# vent_bjt2.net
KiCad netlist of a schematic drawn in EAGLE
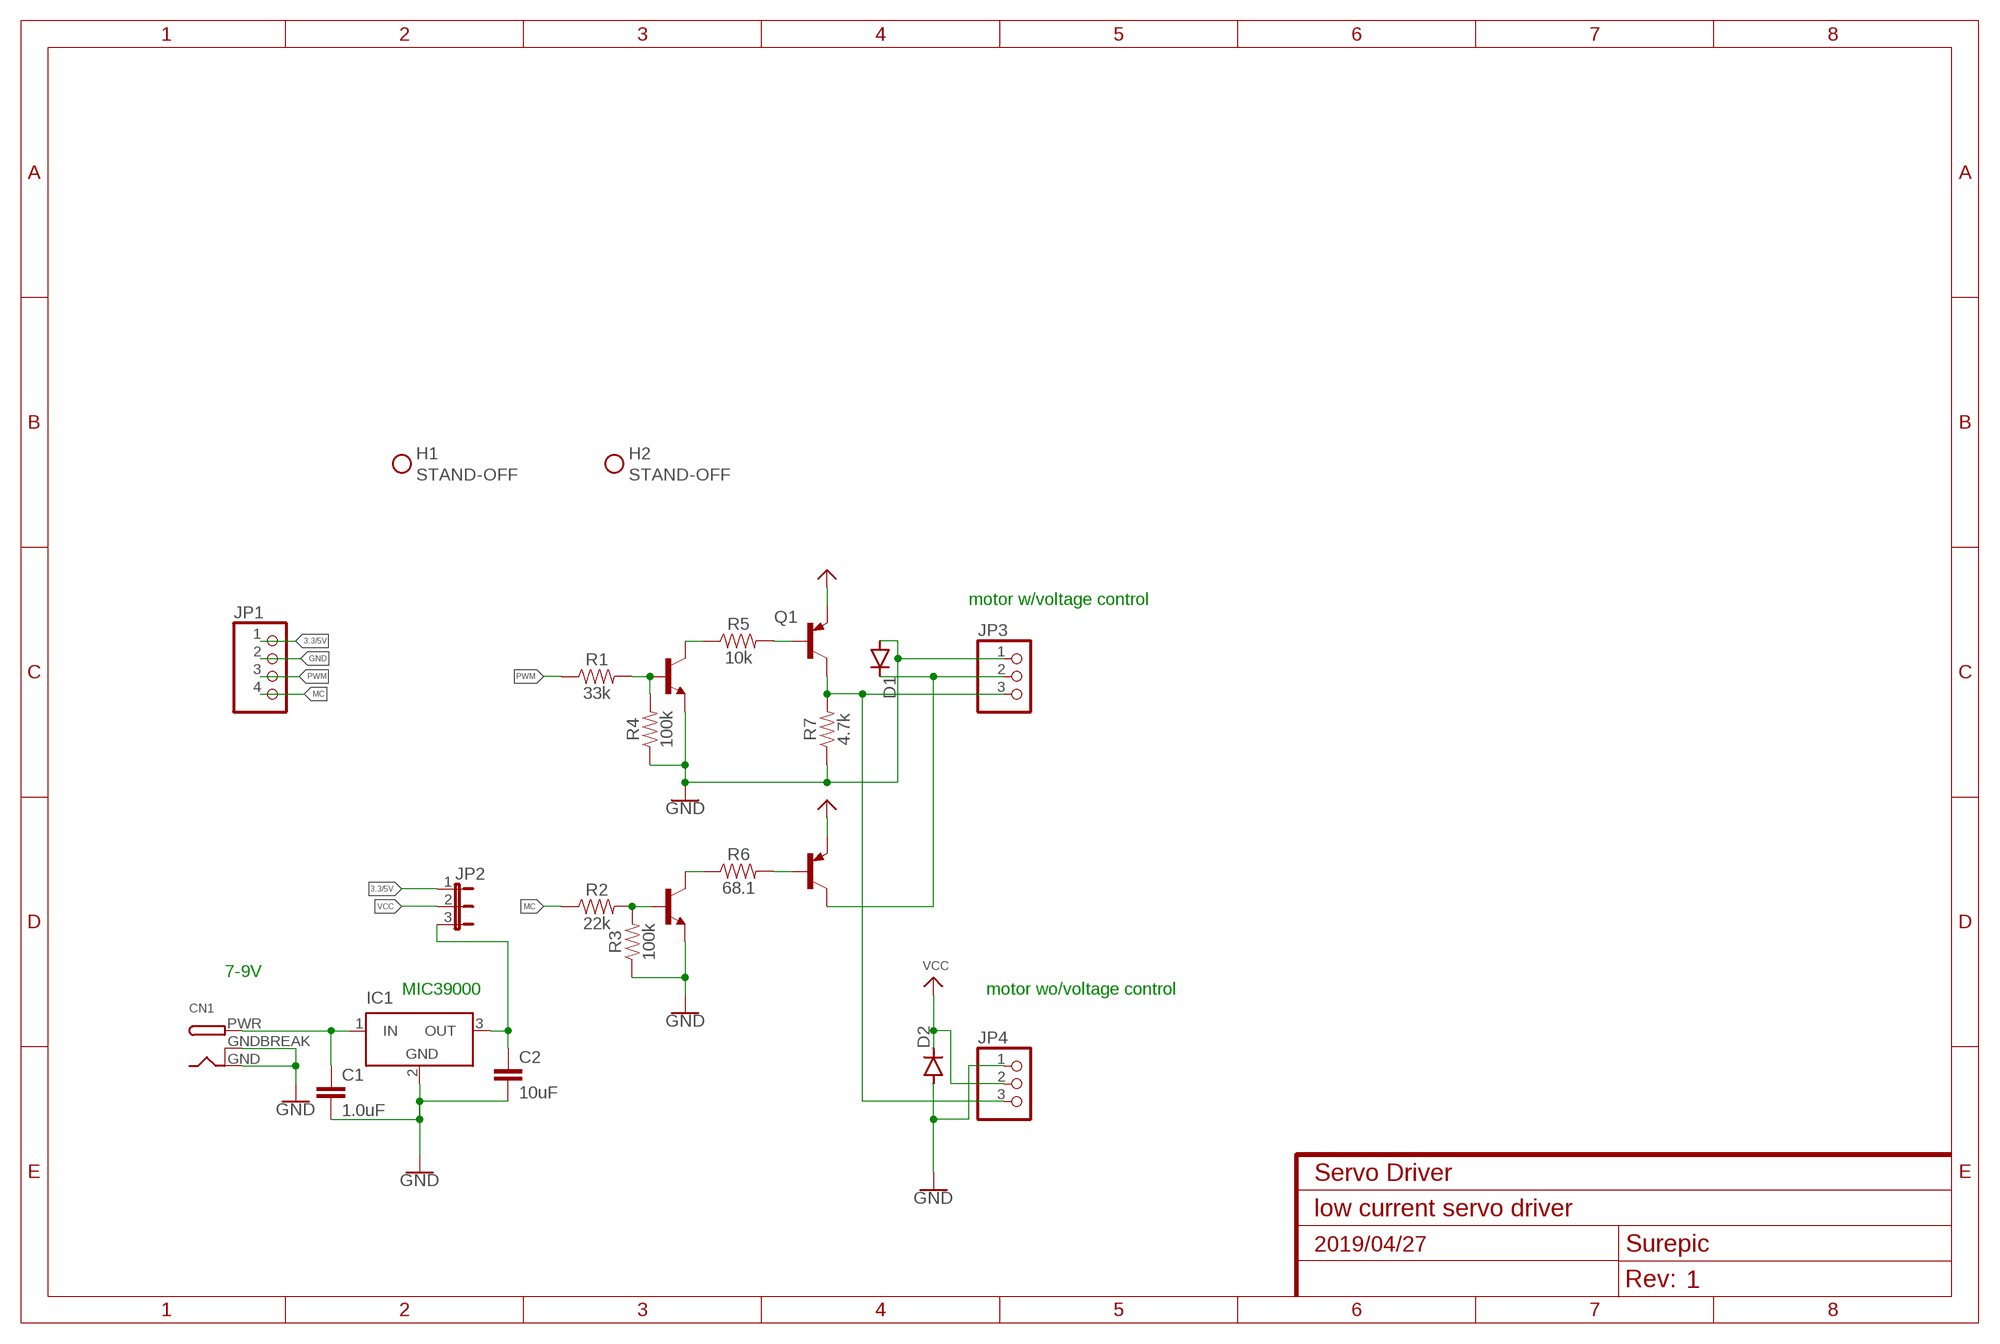
[diagram p0: schematic, sheet 1]

(export (version "E")
  (design (tool "Eeschema 10.0.6"))
  (components
    (comp (ref "C1")
      (value "1.0uF")
      (footprint "eagle-import:0603")
      (libsource (lib "eagle-import") (part "1.0UF-0603-16V-10%"))
    )
    (comp (ref "C2")
      (value "10uF")
      (footprint "eagle-import:0603")
      (libsource (lib "eagle-import") (part "10UF-0603-6.3V-20%"))
    )
    (comp (ref "C945")
      (value "C945")
      (footprint "eagle-import:TO92-ECB")
      (libsource (lib "eagle-import") (part "2SC1815"))
    )
    (comp (ref "CN1")
      (value "DCBARRELPTH")
      (footprint "eagle-import:DCJACK_2MM_PTH")
      (libsource (lib "eagle-import") (part "DCBARRELPTH"))
    )
    (comp (ref "D1")
      (value "1N4148DO35-7")
      (footprint "eagle-import:DO35-7")
      (libsource (lib "eagle-import") (part "1N4148DO35-7"))
    )
    (comp (ref "D2")
      (value "1N4148DO35-7")
      (footprint "eagle-import:DO35-7")
      (libsource (lib "eagle-import") (part "1N4148DO35-7"))
    )
    (comp (ref "H1")
      (value "STAND-OFF")
      (footprint "eagle-import:STAND-OFF")
      (libsource (lib "eagle-import") (part "STAND-OFF"))
    )
    (comp (ref "H2")
      (value "STAND-OFF")
      (footprint "eagle-import:STAND-OFF")
      (libsource (lib "eagle-import") (part "STAND-OFF"))
    )
    (comp (ref "IC1")
      (value "LT1129CST5")
      (footprint "eagle-import:SOT223")
      (fields (field (name "MPN") "LT1129CST-5#PBF"))
      (libsource (lib "eagle-import") (part "LT1129CST5"))
    )
    (comp (ref "JP1")
      (value "PINHD-1X4")
      (footprint "eagle-import:1X04")
      (libsource (lib "eagle-import") (part "PINHD-1X4"))
    )
    (comp (ref "JP2")
      (value "JP2E")
      (footprint "eagle-import:JP2")
      (libsource (lib "eagle-import") (part "JP2E"))
    )
    (comp (ref "JP3")
      (value "PINHD-1X3")
      (footprint "eagle-import:1X03")
      (libsource (lib "eagle-import") (part "PINHD-1X3"))
    )
    (comp (ref "JP4")
      (value "PINHD-1X3")
      (footprint "eagle-import:1X03")
      (libsource (lib "eagle-import") (part "PINHD-1X3"))
    )
    (comp (ref "Q1")
      (value "2N2907")
      (footprint "eagle-import:TO92-EBC-OVAL")
      (libsource (lib "eagle-import") (part "2N2907"))
    )
    (comp (ref "R1")
      (value "33k")
      (footprint "eagle-import:0603")
      (libsource (lib "eagle-import") (part "33KOHM-0603-1/10W-1%"))
    )
    (comp (ref "R2")
      (value "22k")
      (footprint "eagle-import:0603")
      (libsource (lib "eagle-import") (part "22KOHM-0603-1/10W-1%"))
    )
    (comp (ref "R3")
      (value "100k")
      (footprint "eagle-import:0603")
      (libsource (lib "eagle-import") (part "100KOHM-0603-1/10W-1%"))
    )
    (comp (ref "R4")
      (value "100k")
      (footprint "eagle-import:0603")
      (libsource (lib "eagle-import") (part "100KOHM-0603-1/10W-1%"))
    )
    (comp (ref "R5")
      (value "10k")
      (footprint "eagle-import:0603")
      (libsource (lib "eagle-import") (part "10KOHM-0603-1/10W-1%"))
    )
    (comp (ref "R6")
      (value "68.1")
      (footprint "eagle-import:0603")
      (libsource (lib "eagle-import") (part "68.1KOHM-0603-1/10W-1%"))
    )
    (comp (ref "R7")
      (value "4.7k")
      (footprint "eagle-import:0603")
      (libsource (lib "eagle-import") (part "4.7KOHM-0603-1/10W-1%"))
    )
    (comp (ref "S8550")
      (value "S8550")
      (footprint "eagle-import:TO92-EBC-OVAL")
      (libsource (lib "eagle-import") (part "2N2907"))
    )
    (comp (ref "T1")
      (value "S9018")
      (footprint "eagle-import:TO92-EBC-OVAL")
      (libsource (lib "eagle-import") (part "2N2222"))
    )
  )
  (nets
    (net (code "1") (name "3.3{slash}5V") (class "Default")
      (node (ref "JP1") (pin "1") (pinfunction "1_1") (pintype "passive"))
      (node (ref "JP2") (pin "1") (pinfunction "1_1") (pintype "passive"))
    )
    (net (code "2") (name "GND") (class "Default")
      (node (ref "C1") (pin "2") (pinfunction "2_2") (pintype "passive"))
      (node (ref "C2") (pin "2") (pinfunction "2_2") (pintype "passive"))
      (node (ref "C945") (pin "E") (pinfunction "E_E") (pintype "passive"))
      (node (ref "CN1") (pin "GND") (pinfunction "GND_GND") (pintype "power_in"))
      (node (ref "CN1") (pin "GNDBREAK") (pinfunction "GNDBREAK_GNDBREAK") (pintype "power_in"))
      (node (ref "D1") (pin "A") (pinfunction "A_A") (pintype "passive"))
      (node (ref "D2") (pin "A") (pinfunction "A_A") (pintype "passive"))
      (node (ref "IC1") (pin "2") (pinfunction "GND_2") (pintype "power_in"))
      (node (ref "JP1") (pin "2") (pinfunction "2_2") (pintype "passive"))
      (node (ref "JP3") (pin "1") (pinfunction "1_1") (pintype "passive"))
      (node (ref "JP4") (pin "1") (pinfunction "1_1") (pintype "passive"))
      (node (ref "R3") (pin "1") (pinfunction "1_1") (pintype "passive"))
      (node (ref "R4") (pin "1") (pinfunction "1_1") (pintype "passive"))
      (node (ref "R7") (pin "1") (pinfunction "1_1") (pintype "passive"))
      (node (ref "T1") (pin "E") (pinfunction "E_E") (pintype "passive"))
    )
    (net (code "3") (name "MC") (class "Default")
      (node (ref "JP1") (pin "4") (pinfunction "4_4") (pintype "passive"))
      (node (ref "R2") (pin "1") (pinfunction "1_1") (pintype "passive"))
    )
    (net (code "4") (name "Net-(C945-PadB)") (class "Default")
      (node (ref "C945") (pin "B") (pinfunction "B_B") (pintype "passive"))
      (node (ref "R2") (pin "2") (pinfunction "2_2") (pintype "passive"))
      (node (ref "R3") (pin "2") (pinfunction "2_2") (pintype "passive"))
    )
    (net (code "5") (name "Net-(C945-PadC)") (class "Default")
      (node (ref "C945") (pin "C") (pinfunction "C_C") (pintype "passive"))
      (node (ref "R6") (pin "1") (pinfunction "1_1") (pintype "passive"))
    )
    (net (code "6") (name "Net-(D1-PadC)") (class "Default")
      (node (ref "D1") (pin "C") (pinfunction "C_C") (pintype "passive"))
      (node (ref "JP3") (pin "2") (pinfunction "2_2") (pintype "passive"))
      (node (ref "S8550") (pin "C") (pinfunction "C_C") (pintype "passive"))
    )
    (net (code "7") (name "Net-(IC1A-IN)") (class "Default")
      (node (ref "C1") (pin "1") (pinfunction "1_1") (pintype "passive"))
      (node (ref "CN1") (pin "PWR") (pinfunction "PWR_PWR") (pintype "power_in"))
      (node (ref "IC1") (pin "1") (pinfunction "IN_1") (pintype "input"))
    )
    (net (code "8") (name "Net-(IC1A-OUT)") (class "Default")
      (node (ref "C2") (pin "1") (pinfunction "1_1") (pintype "passive"))
      (node (ref "IC1") (pin "3") (pinfunction "OUT_3") (pintype "output"))
      (node (ref "JP2") (pin "3") (pinfunction "3_3") (pintype "passive"))
    )
    (net (code "9") (name "Net-(JP3-Pad3)") (class "Default")
      (node (ref "JP3") (pin "3") (pinfunction "3_3") (pintype "passive"))
      (node (ref "JP4") (pin "3") (pinfunction "3_3") (pintype "passive"))
      (node (ref "Q1") (pin "C") (pinfunction "C_C") (pintype "passive"))
      (node (ref "R7") (pin "2") (pinfunction "2_2") (pintype "passive"))
    )
    (net (code "10") (name "Net-(Q1-PadB)") (class "Default")
      (node (ref "Q1") (pin "B") (pinfunction "B_B") (pintype "passive"))
      (node (ref "R5") (pin "2") (pinfunction "2_2") (pintype "passive"))
    )
    (net (code "11") (name "Net-(R1-Pad2)") (class "Default")
      (node (ref "R1") (pin "2") (pinfunction "2_2") (pintype "passive"))
      (node (ref "R4") (pin "2") (pinfunction "2_2") (pintype "passive"))
      (node (ref "T1") (pin "B") (pinfunction "B_B") (pintype "passive"))
    )
    (net (code "12") (name "Net-(R5-Pad1)") (class "Default")
      (node (ref "R5") (pin "1") (pinfunction "1_1") (pintype "passive"))
      (node (ref "T1") (pin "C") (pinfunction "C_C") (pintype "passive"))
    )
    (net (code "13") (name "Net-(R6-Pad2)") (class "Default")
      (node (ref "R6") (pin "2") (pinfunction "2_2") (pintype "passive"))
      (node (ref "S8550") (pin "B") (pinfunction "B_B") (pintype "passive"))
    )
    (net (code "14") (name "PWM") (class "Default")
      (node (ref "JP1") (pin "3") (pinfunction "3_3") (pintype "passive"))
      (node (ref "R1") (pin "1") (pinfunction "1_1") (pintype "passive"))
    )
    (net (code "15") (name "VCC") (class "Default")
      (node (ref "D2") (pin "C") (pinfunction "C_C") (pintype "passive"))
      (node (ref "JP2") (pin "2") (pinfunction "2_2") (pintype "passive"))
      (node (ref "JP4") (pin "2") (pinfunction "2_2") (pintype "passive"))
      (node (ref "Q1") (pin "E") (pinfunction "E_E") (pintype "passive"))
      (node (ref "S8550") (pin "E") (pinfunction "E_E") (pintype "passive"))
    )
  )
)
